# h-bridge2-smd-002.net
KiCad netlist of a schematic drawn in EAGLE
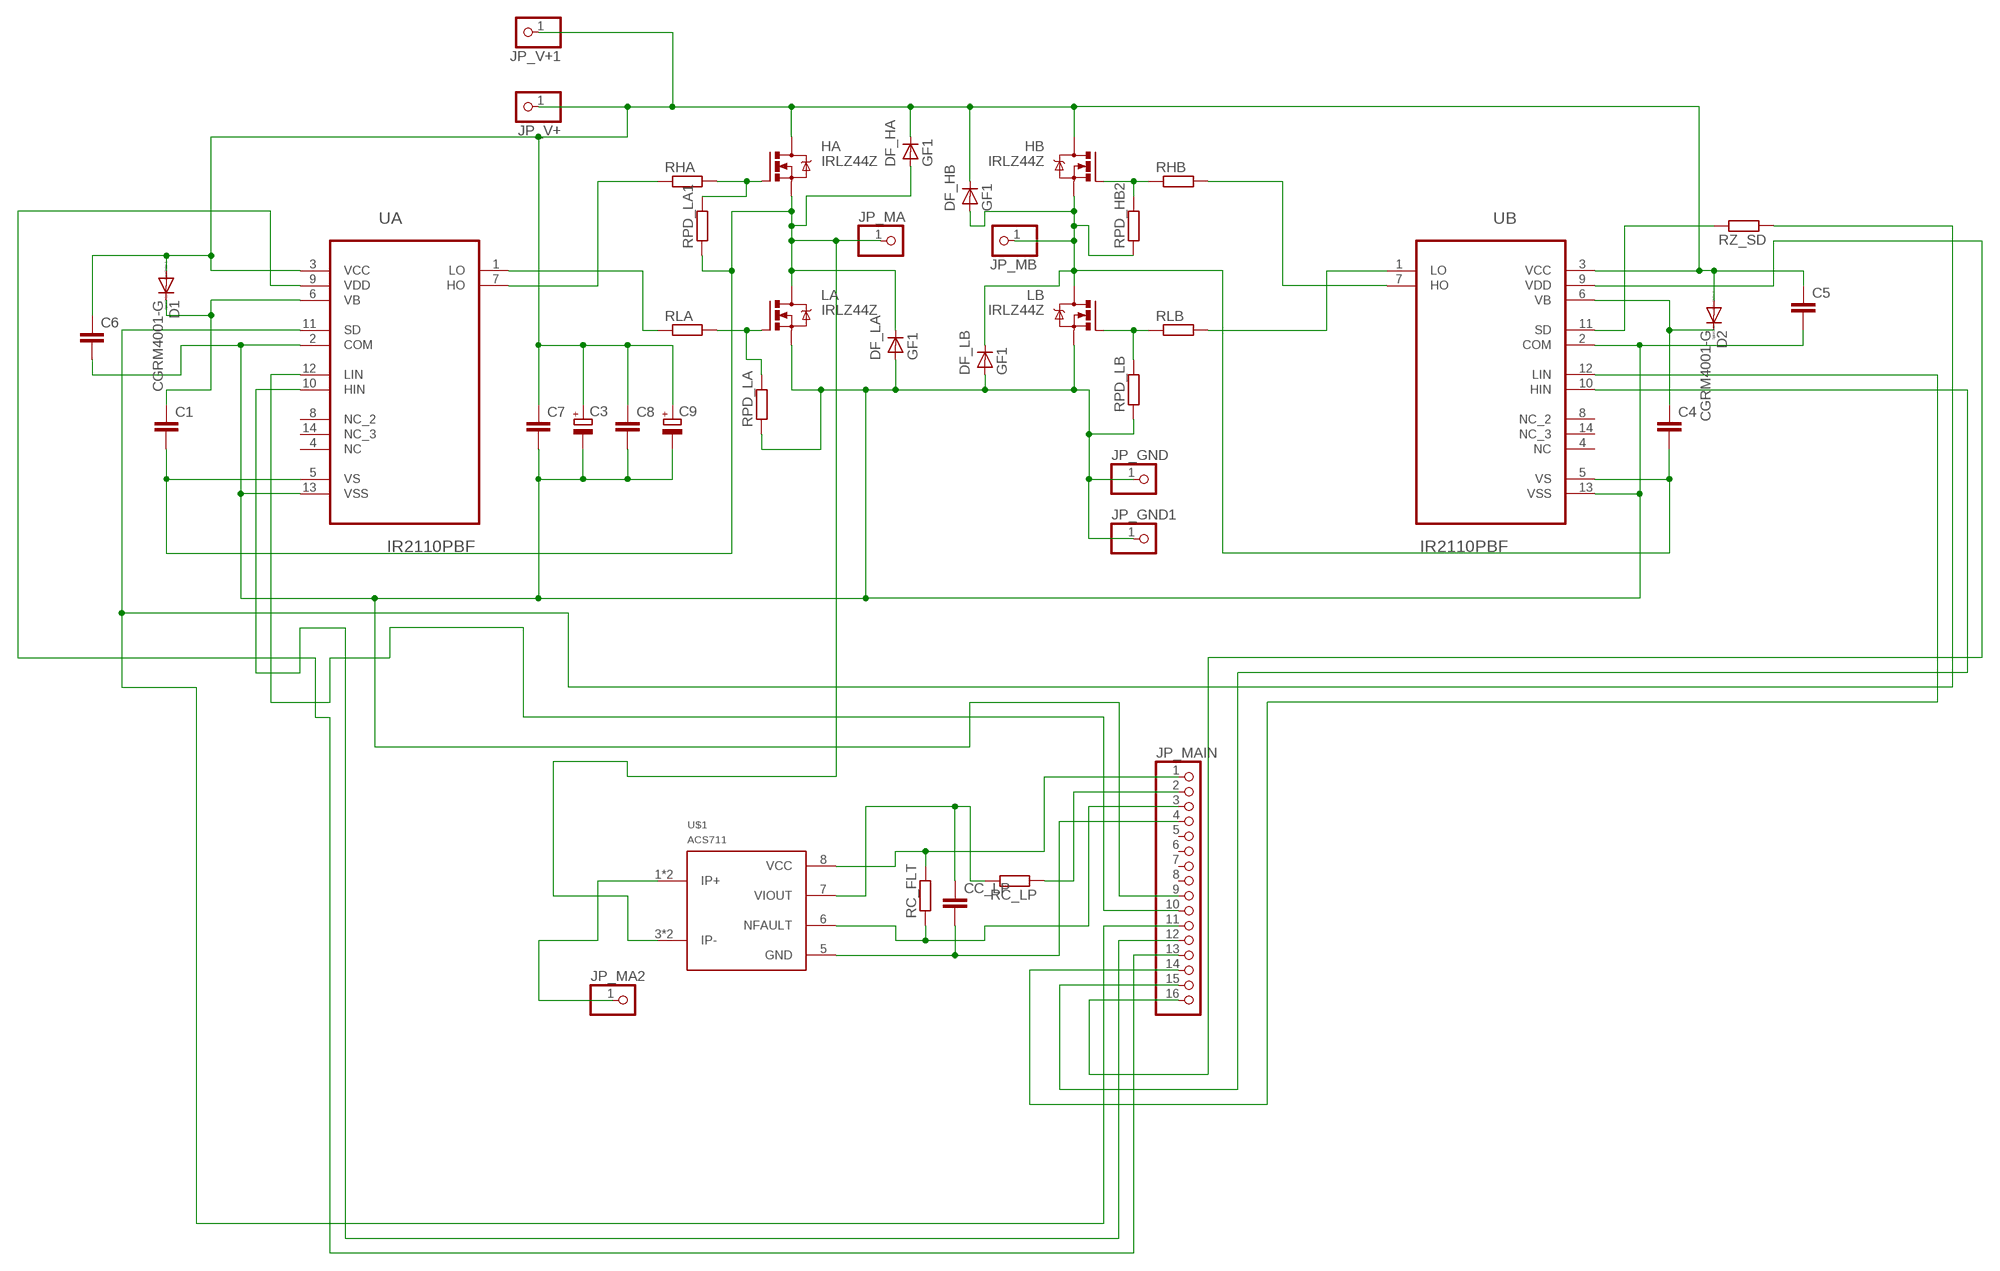
[diagram p0: schematic, sheet 1]

(export (version "E")
  (design (tool "Eeschema 10.0.6"))
  (components
    (comp (ref "C1")
      (value "C-EUC4532")
      (footprint "eagle-import:C4532")
      (libsource (lib "eagle-import") (part "C-EUC4532"))
    )
    (comp (ref "C3")
      (value "CPOL-EUE5-13")
      (footprint "eagle-import:E5-13")
      (libsource (lib "eagle-import") (part "CPOL-EUE5-13"))
    )
    (comp (ref "C4")
      (value "C-EUC4532")
      (footprint "eagle-import:C4532")
      (libsource (lib "eagle-import") (part "C-EUC4532"))
    )
    (comp (ref "C5")
      (value "C-EUC4532")
      (footprint "eagle-import:C4532")
      (libsource (lib "eagle-import") (part "C-EUC4532"))
    )
    (comp (ref "C6")
      (value "C-EUC4532")
      (footprint "eagle-import:C4532")
      (libsource (lib "eagle-import") (part "C-EUC4532"))
    )
    (comp (ref "C7")
      (value "C-EUC4532")
      (footprint "eagle-import:C4532")
      (libsource (lib "eagle-import") (part "C-EUC4532"))
    )
    (comp (ref "C8")
      (value "C-EUC4532")
      (footprint "eagle-import:C4532")
      (libsource (lib "eagle-import") (part "C-EUC4532"))
    )
    (comp (ref "C9")
      (value "CPOL-EUE5-13")
      (footprint "eagle-import:E5-13")
      (libsource (lib "eagle-import") (part "CPOL-EUE5-13"))
    )
    (comp (ref "CC_LP")
      (value "C-EUC4532")
      (footprint "eagle-import:C4532")
      (libsource (lib "eagle-import") (part "C-EUC4532"))
    )
    (comp (ref "D1")
      (value "CGRM4001-G")
      (footprint "eagle-import:SOD-123_MINI-SMA")
      (libsource (lib "eagle-import") (part "CGRM400-G1"))
    )
    (comp (ref "D2")
      (value "CGRM4001-G")
      (footprint "eagle-import:SOD-123_MINI-SMA")
      (libsource (lib "eagle-import") (part "CGRM400-G1"))
    )
    (comp (ref "DF_HA")
      (value "GF1")
      (footprint "eagle-import:SMA-DO214AC")
      (libsource (lib "eagle-import") (part "GF1"))
    )
    (comp (ref "DF_HB")
      (value "GF1")
      (footprint "eagle-import:SMA-DO214AC")
      (libsource (lib "eagle-import") (part "GF1"))
    )
    (comp (ref "DF_LA")
      (value "GF1")
      (footprint "eagle-import:SMA-DO214AC")
      (libsource (lib "eagle-import") (part "GF1"))
    )
    (comp (ref "DF_LB")
      (value "GF1")
      (footprint "eagle-import:SMA-DO214AC")
      (libsource (lib "eagle-import") (part "GF1"))
    )
    (comp (ref "HA")
      (value "IRLZ44Z")
      (footprint "eagle-import:TO220BH")
      (libsource (lib "eagle-import") (part "IRLZ44Z"))
    )
    (comp (ref "HB")
      (value "IRLZ44Z")
      (footprint "eagle-import:TO220BH")
      (libsource (lib "eagle-import") (part "IRLZ44Z"))
    )
    (comp (ref "JP_GND")
      (value "PINHD-1X1")
      (footprint "eagle-import:1X01")
      (libsource (lib "eagle-import") (part "PINHD-1X1"))
    )
    (comp (ref "JP_GND1")
      (value "PINHD-1X1")
      (footprint "eagle-import:1X01")
      (libsource (lib "eagle-import") (part "PINHD-1X1"))
    )
    (comp (ref "JP_MA")
      (value "PINHD-1X1")
      (footprint "eagle-import:1X01")
      (libsource (lib "eagle-import") (part "PINHD-1X1"))
    )
    (comp (ref "JP_MA2")
      (value "PINHD-1X1")
      (footprint "eagle-import:1X01")
      (libsource (lib "eagle-import") (part "PINHD-1X1"))
    )
    (comp (ref "JP_MAIN")
      (value "PINHD-1X16")
      (footprint "eagle-import:1X16")
      (libsource (lib "eagle-import") (part "PINHD-1X16"))
    )
    (comp (ref "JP_MB")
      (value "PINHD-1X1")
      (footprint "eagle-import:1X01")
      (libsource (lib "eagle-import") (part "PINHD-1X1"))
    )
    (comp (ref "JP_V+")
      (value "PINHD-1X1")
      (footprint "eagle-import:1X01")
      (libsource (lib "eagle-import") (part "PINHD-1X1"))
    )
    (comp (ref "JP_V+1")
      (value "PINHD-1X1")
      (footprint "eagle-import:1X01")
      (libsource (lib "eagle-import") (part "PINHD-1X1"))
    )
    (comp (ref "LA")
      (value "IRLZ44Z")
      (footprint "eagle-import:TO220BH")
      (libsource (lib "eagle-import") (part "IRLZ44Z"))
    )
    (comp (ref "LB")
      (value "IRLZ44Z")
      (footprint "eagle-import:TO220BH")
      (libsource (lib "eagle-import") (part "IRLZ44Z"))
    )
    (comp (ref "RC_FLT")
      (value "R-EU_R1206")
      (footprint "eagle-import:R1206")
      (libsource (lib "eagle-import") (part "R-EU_R1206"))
    )
    (comp (ref "RC_LP")
      (value "R-EU_R1206")
      (footprint "eagle-import:R1206")
      (libsource (lib "eagle-import") (part "R-EU_R1206"))
    )
    (comp (ref "RHA")
      (value "R-EU_R1206")
      (footprint "eagle-import:R1206")
      (libsource (lib "eagle-import") (part "R-EU_R1206"))
    )
    (comp (ref "RHB")
      (value "R-EU_R1206")
      (footprint "eagle-import:R1206")
      (libsource (lib "eagle-import") (part "R-EU_R1206"))
    )
    (comp (ref "RLA")
      (value "R-EU_R1206")
      (footprint "eagle-import:R1206")
      (libsource (lib "eagle-import") (part "R-EU_R1206"))
    )
    (comp (ref "RLB")
      (value "R-EU_R1206")
      (footprint "eagle-import:R1206")
      (libsource (lib "eagle-import") (part "R-EU_R1206"))
    )
    (comp (ref "RPD_HB2")
      (value "R-EU_R1206")
      (footprint "eagle-import:R1206")
      (libsource (lib "eagle-import") (part "R-EU_R1206"))
    )
    (comp (ref "RPD_LA")
      (value "R-EU_R1206")
      (footprint "eagle-import:R1206")
      (libsource (lib "eagle-import") (part "R-EU_R1206"))
    )
    (comp (ref "RPD_LA1")
      (value "R-EU_R1206")
      (footprint "eagle-import:R1206")
      (libsource (lib "eagle-import") (part "R-EU_R1206"))
    )
    (comp (ref "RPD_LB")
      (value "R-EU_R1206")
      (footprint "eagle-import:R1206")
      (libsource (lib "eagle-import") (part "R-EU_R1206"))
    )
    (comp (ref "RZ_SD")
      (value "R-EU_R1206")
      (footprint "eagle-import:R1206")
      (libsource (lib "eagle-import") (part "R-EU_R1206"))
    )
    (comp (ref "U$1")
      (value "ACS711")
      (footprint "eagle-import:SOIC8")
      (libsource (lib "eagle-import") (part "ACS711"))
    )
    (comp (ref "UA")
      (value "IR2110PBF")
      (footprint "eagle-import:DIP254P762X533-14")
      (libsource (lib "eagle-import") (part "IR2110PBF"))
    )
    (comp (ref "UB")
      (value "IR2110PBF")
      (footprint "eagle-import:DIP254P762X533-14")
      (libsource (lib "eagle-import") (part "IR2110PBF"))
    )
  )
  (nets
    (net (code "1") (name "Net-(DF_HA-C)") (class "Default")
      (node (ref "C3") (pin "+") (pinfunction "+_+") (pintype "passive"))
      (node (ref "C5") (pin "1") (pinfunction "1_1") (pintype "passive"))
      (node (ref "C6") (pin "1") (pinfunction "1_1") (pintype "passive"))
      (node (ref "C7") (pin "1") (pinfunction "1_1") (pintype "passive"))
      (node (ref "C8") (pin "1") (pinfunction "1_1") (pintype "passive"))
      (node (ref "C9") (pin "+") (pinfunction "+_+") (pintype "passive"))
      (node (ref "D1") (pin "A") (pinfunction "A_A") (pintype "passive"))
      (node (ref "D2") (pin "A") (pinfunction "A_A") (pintype "passive"))
      (node (ref "DF_HA") (pin "K") (pinfunction "C_K") (pintype "passive"))
      (node (ref "DF_HB") (pin "K") (pinfunction "C_K") (pintype "passive"))
      (node (ref "HA") (pin "D") (pinfunction "D_D") (pintype "passive"))
      (node (ref "HB") (pin "D") (pinfunction "D_D") (pintype "passive"))
      (node (ref "JP_V+") (pin "1") (pinfunction "1_1") (pintype "passive"))
      (node (ref "JP_V+1") (pin "1") (pinfunction "1_1") (pintype "passive"))
      (node (ref "UA") (pin "3") (pinfunction "VCC_3") (pintype "power_in"))
      (node (ref "UB") (pin "3") (pinfunction "VCC_3") (pintype "power_in"))
    )
    (net (code "2") (name "Net-(DF_LA-C)") (class "Default")
      (node (ref "C1") (pin "2") (pinfunction "2_2") (pintype "passive"))
      (node (ref "DF_HA") (pin "A") (pinfunction "A_A") (pintype "passive"))
      (node (ref "DF_LA") (pin "K") (pinfunction "C_K") (pintype "passive"))
      (node (ref "HA") (pin "S") (pinfunction "S_S") (pintype "passive"))
      (node (ref "JP_MA") (pin "1") (pinfunction "1_1") (pintype "passive"))
      (node (ref "LA") (pin "D") (pinfunction "D_D") (pintype "passive"))
      (node (ref "RPD_LA1") (pin "1") (pinfunction "1_1") (pintype "passive"))
      (node (ref "U$1") (pin "3") (pinfunction "IP-_3") (pintype "bidirectional"))
      (node (ref "U$1") (pin "4") (pinfunction "IP-_4") (pintype "bidirectional"))
      (node (ref "UA") (pin "5") (pinfunction "VS_5") (pintype "power_in"))
    )
    (net (code "3") (name "Net-(DF_LB-C)") (class "Default")
      (node (ref "C4") (pin "2") (pinfunction "2_2") (pintype "passive"))
      (node (ref "DF_HB") (pin "A") (pinfunction "A_A") (pintype "passive"))
      (node (ref "DF_LB") (pin "K") (pinfunction "C_K") (pintype "passive"))
      (node (ref "HB") (pin "S") (pinfunction "S_S") (pintype "passive"))
      (node (ref "JP_MB") (pin "1") (pinfunction "1_1") (pintype "passive"))
      (node (ref "LB") (pin "D") (pinfunction "D_D") (pintype "passive"))
      (node (ref "RPD_HB2") (pin "1") (pinfunction "1_1") (pintype "passive"))
      (node (ref "UB") (pin "5") (pinfunction "VS_5") (pintype "power_in"))
    )
    (net (code "4") (name "Net-(HA-PadG)") (class "Default")
      (node (ref "HA") (pin "G") (pinfunction "G_G") (pintype "passive"))
      (node (ref "RHA") (pin "2") (pinfunction "2_2") (pintype "passive"))
      (node (ref "RPD_LA1") (pin "2") (pinfunction "2_2") (pintype "passive"))
    )
    (net (code "5") (name "Net-(HB-PadG)") (class "Default")
      (node (ref "HB") (pin "G") (pinfunction "G_G") (pintype "passive"))
      (node (ref "RHB") (pin "1") (pinfunction "1_1") (pintype "passive"))
      (node (ref "RPD_HB2") (pin "2") (pinfunction "2_2") (pintype "passive"))
    )
    (net (code "6") (name "Net-(JP_MA2-Pad1)") (class "Default")
      (node (ref "JP_MA2") (pin "1") (pinfunction "1_1") (pintype "passive"))
      (node (ref "U$1") (pin "1") (pinfunction "IP+_1") (pintype "bidirectional"))
      (node (ref "U$1") (pin "2") (pinfunction "IP+_2") (pintype "bidirectional"))
    )
    (net (code "7") (name "Net-(JP_MAIN-Pad2)") (class "Default")
      (node (ref "JP_MAIN") (pin "2") (pinfunction "2_2") (pintype "passive"))
      (node (ref "RC_LP") (pin "1") (pinfunction "1_1") (pintype "passive"))
    )
    (net (code "8") (name "Net-(LA-PadG)") (class "Default")
      (node (ref "LA") (pin "G") (pinfunction "G_G") (pintype "passive"))
      (node (ref "RLA") (pin "2") (pinfunction "2_2") (pintype "passive"))
      (node (ref "RPD_LA") (pin "2") (pinfunction "2_2") (pintype "passive"))
    )
    (net (code "9") (name "Net-(LB-PadG)") (class "Default")
      (node (ref "LB") (pin "G") (pinfunction "G_G") (pintype "passive"))
      (node (ref "RLB") (pin "1") (pinfunction "1_1") (pintype "passive"))
      (node (ref "RPD_LB") (pin "2") (pinfunction "2_2") (pintype "passive"))
    )
    (net (code "10") (name "Net-(U$1-GND)") (class "Default")
      (node (ref "CC_LP") (pin "2") (pinfunction "2_2") (pintype "passive"))
      (node (ref "JP_MAIN") (pin "4") (pinfunction "4_4") (pintype "passive"))
      (node (ref "U$1") (pin "5") (pinfunction "GND_5") (pintype "bidirectional"))
    )
    (net (code "11") (name "Net-(U$1-NFAULT)") (class "Default")
      (node (ref "JP_MAIN") (pin "3") (pinfunction "3_3") (pintype "passive"))
      (node (ref "RC_FLT") (pin "1") (pinfunction "1_1") (pintype "passive"))
      (node (ref "U$1") (pin "6") (pinfunction "NFAULT_6") (pintype "bidirectional"))
    )
    (net (code "12") (name "Net-(U$1-VCC)") (class "Default")
      (node (ref "JP_MAIN") (pin "1") (pinfunction "1_1") (pintype "passive"))
      (node (ref "RC_FLT") (pin "2") (pinfunction "2_2") (pintype "passive"))
      (node (ref "U$1") (pin "8") (pinfunction "VCC_8") (pintype "bidirectional"))
    )
    (net (code "13") (name "Net-(U$1-VIOUT)") (class "Default")
      (node (ref "CC_LP") (pin "1") (pinfunction "1_1") (pintype "passive"))
      (node (ref "RC_LP") (pin "2") (pinfunction "2_2") (pintype "passive"))
      (node (ref "U$1") (pin "7") (pinfunction "VIOUT_7") (pintype "bidirectional"))
    )
    (net (code "14") (name "Net-(UA-COM)") (class "Default")
      (node (ref "C3") (pin "-") (pinfunction "-_-") (pintype "passive"))
      (node (ref "C5") (pin "2") (pinfunction "2_2") (pintype "passive"))
      (node (ref "C6") (pin "2") (pinfunction "2_2") (pintype "passive"))
      (node (ref "C7") (pin "2") (pinfunction "2_2") (pintype "passive"))
      (node (ref "C8") (pin "2") (pinfunction "2_2") (pintype "passive"))
      (node (ref "C9") (pin "-") (pinfunction "-_-") (pintype "passive"))
      (node (ref "DF_LA") (pin "A") (pinfunction "A_A") (pintype "passive"))
      (node (ref "DF_LB") (pin "A") (pinfunction "A_A") (pintype "passive"))
      (node (ref "JP_GND") (pin "1") (pinfunction "1_1") (pintype "passive"))
      (node (ref "JP_GND1") (pin "1") (pinfunction "1_1") (pintype "passive"))
      (node (ref "JP_MAIN") (pin "9") (pinfunction "9_9") (pintype "passive"))
      (node (ref "LA") (pin "S") (pinfunction "S_S") (pintype "passive"))
      (node (ref "LB") (pin "S") (pinfunction "S_S") (pintype "passive"))
      (node (ref "RPD_LA") (pin "1") (pinfunction "1_1") (pintype "passive"))
      (node (ref "RPD_LB") (pin "1") (pinfunction "1_1") (pintype "passive"))
      (node (ref "UA") (pin "13") (pinfunction "VSS_13") (pintype "power_in"))
      (node (ref "UA") (pin "2") (pinfunction "COM_2") (pintype "passive"))
      (node (ref "UB") (pin "13") (pinfunction "VSS_13") (pintype "power_in"))
      (node (ref "UB") (pin "2") (pinfunction "COM_2") (pintype "passive"))
    )
    (net (code "15") (name "Net-(UA-HIN)") (class "Default")
      (node (ref "JP_MAIN") (pin "12") (pinfunction "12_12") (pintype "passive"))
      (node (ref "UA") (pin "10") (pinfunction "HIN_10") (pintype "input"))
    )
    (net (code "16") (name "Net-(UA-HO)") (class "Default")
      (node (ref "RHA") (pin "1") (pinfunction "1_1") (pintype "passive"))
      (node (ref "UA") (pin "7") (pinfunction "HO_7") (pintype "output"))
    )
    (net (code "17") (name "Net-(UA-LIN)") (class "Default")
      (node (ref "JP_MAIN") (pin "10") (pinfunction "10_10") (pintype "passive"))
      (node (ref "UA") (pin "12") (pinfunction "LIN_12") (pintype "input"))
    )
    (net (code "18") (name "Net-(UA-LO)") (class "Default")
      (node (ref "RLA") (pin "1") (pinfunction "1_1") (pintype "passive"))
      (node (ref "UA") (pin "1") (pinfunction "LO_1") (pintype "output"))
    )
    (net (code "19") (name "Net-(UA-SD)") (class "Default")
      (node (ref "JP_MAIN") (pin "11") (pinfunction "11_11") (pintype "passive"))
      (node (ref "RZ_SD") (pin "1") (pinfunction "1_1") (pintype "passive"))
      (node (ref "UA") (pin "11") (pinfunction "SD_11") (pintype "input"))
    )
    (net (code "20") (name "Net-(UA-VB)") (class "Default")
      (node (ref "C1") (pin "1") (pinfunction "1_1") (pintype "passive"))
      (node (ref "D1") (pin "C") (pinfunction "C_C") (pintype "passive"))
      (node (ref "UA") (pin "6") (pinfunction "VB_6") (pintype "power_in"))
    )
    (net (code "21") (name "Net-(UA-VDD)") (class "Default")
      (node (ref "JP_MAIN") (pin "13") (pinfunction "13_13") (pintype "passive"))
      (node (ref "UA") (pin "9") (pinfunction "VDD_9") (pintype "power_in"))
    )
    (net (code "22") (name "Net-(UB-HIN)") (class "Default")
      (node (ref "JP_MAIN") (pin "15") (pinfunction "15_15") (pintype "passive"))
      (node (ref "UB") (pin "10") (pinfunction "HIN_10") (pintype "input"))
    )
    (net (code "23") (name "Net-(UB-HO)") (class "Default")
      (node (ref "RHB") (pin "2") (pinfunction "2_2") (pintype "passive"))
      (node (ref "UB") (pin "7") (pinfunction "HO_7") (pintype "output"))
    )
    (net (code "24") (name "Net-(UB-LIN)") (class "Default")
      (node (ref "JP_MAIN") (pin "14") (pinfunction "14_14") (pintype "passive"))
      (node (ref "UB") (pin "12") (pinfunction "LIN_12") (pintype "input"))
    )
    (net (code "25") (name "Net-(UB-LO)") (class "Default")
      (node (ref "RLB") (pin "2") (pinfunction "2_2") (pintype "passive"))
      (node (ref "UB") (pin "1") (pinfunction "LO_1") (pintype "output"))
    )
    (net (code "26") (name "Net-(UB-SD)") (class "Default")
      (node (ref "RZ_SD") (pin "2") (pinfunction "2_2") (pintype "passive"))
      (node (ref "UB") (pin "11") (pinfunction "SD_11") (pintype "input"))
    )
    (net (code "27") (name "Net-(UB-VB)") (class "Default")
      (node (ref "C4") (pin "1") (pinfunction "1_1") (pintype "passive"))
      (node (ref "D2") (pin "C") (pinfunction "C_C") (pintype "passive"))
      (node (ref "UB") (pin "6") (pinfunction "VB_6") (pintype "power_in"))
    )
    (net (code "28") (name "Net-(UB-VDD)") (class "Default")
      (node (ref "JP_MAIN") (pin "16") (pinfunction "16_16") (pintype "passive"))
      (node (ref "UB") (pin "9") (pinfunction "VDD_9") (pintype "power_in"))
    )
    (net (code "29") (name "unconnected-(JP_MAIN-Pad5)") (class "Default")
      (node (ref "JP_MAIN") (pin "5") (pinfunction "5_5") (pintype "passive"))
    )
    (net (code "30") (name "unconnected-(JP_MAIN-Pad6)") (class "Default")
      (node (ref "JP_MAIN") (pin "6") (pinfunction "6_6") (pintype "passive"))
    )
    (net (code "31") (name "unconnected-(JP_MAIN-Pad7)") (class "Default")
      (node (ref "JP_MAIN") (pin "7") (pinfunction "7_7") (pintype "passive"))
    )
    (net (code "32") (name "unconnected-(JP_MAIN-Pad8)") (class "Default")
      (node (ref "JP_MAIN") (pin "8") (pinfunction "8_8") (pintype "passive"))
    )
    (net (code "33") (name "unconnected-(UA-NC-Pad4)") (class "Default")
      (node (ref "UA") (pin "4") (pinfunction "NC_4") (pintype "no_connect"))
    )
    (net (code "34") (name "unconnected-(UA-NC_2-Pad8)") (class "Default")
      (node (ref "UA") (pin "8") (pinfunction "NC_2_8") (pintype "no_connect"))
    )
    (net (code "35") (name "unconnected-(UA-NC_3-Pad14)") (class "Default")
      (node (ref "UA") (pin "14") (pinfunction "NC_3_14") (pintype "no_connect"))
    )
    (net (code "36") (name "unconnected-(UB-NC-Pad4)") (class "Default")
      (node (ref "UB") (pin "4") (pinfunction "NC_4") (pintype "no_connect"))
    )
    (net (code "37") (name "unconnected-(UB-NC_2-Pad8)") (class "Default")
      (node (ref "UB") (pin "8") (pinfunction "NC_2_8") (pintype "no_connect"))
    )
    (net (code "38") (name "unconnected-(UB-NC_3-Pad14)") (class "Default")
      (node (ref "UB") (pin "14") (pinfunction "NC_3_14") (pintype "no_connect"))
    )
  )
)
